# brushed_motor_drivers.net
KiCad netlist of a schematic drawn in Altium Designer
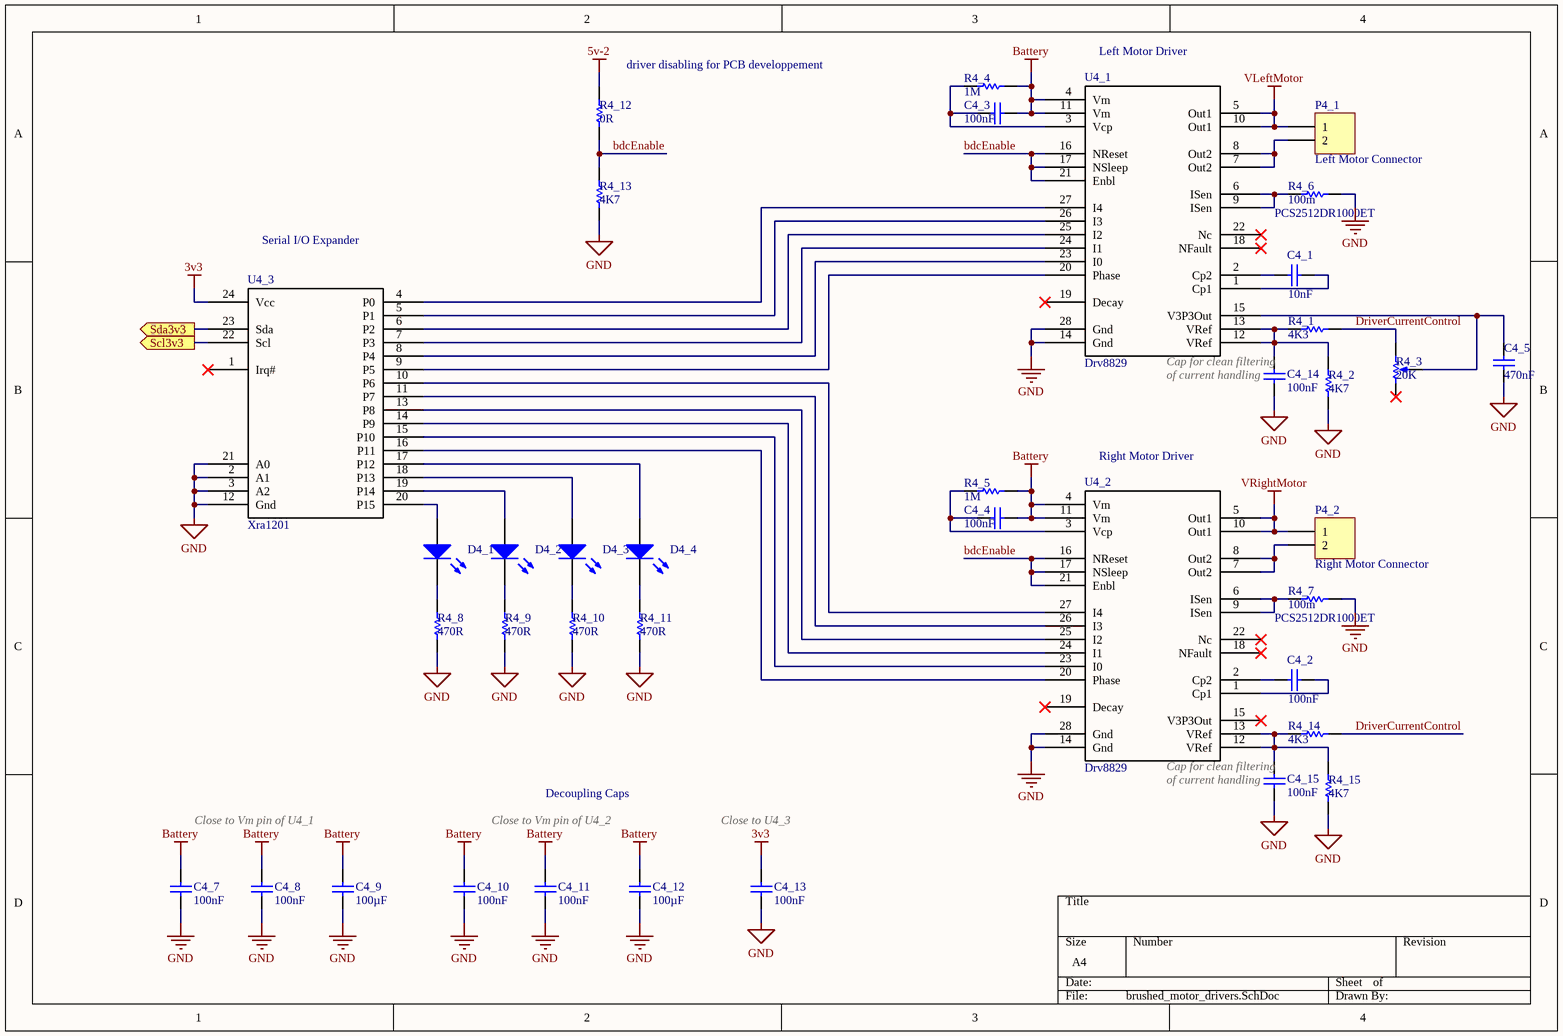
[diagram p0: brushed_motor_drivers.SchDoc]

(export (version "E")
  (design (tool "Eeschema 10.0.6"))
  (components
    (comp (ref "C4_1")
      (value "10nF")
      (footprint "C1206")
      (description "Capacitor")
      (fields (field (name "Comment") "C1206C103M5RACTU") (field (name "PUBLISHER") "Altium Limited"))
      (libsource (lib "Miscellaneous Devices") (part "Cap"))
    )
    (comp (ref "C4_2")
      (value "100nF")
      (footprint "C1206")
      (description "Capacitor")
      (fields (field (name "Comment") "C1206C103M5RACTU") (field (name "PUBLISHER") "Altium Limited"))
      (libsource (lib "Miscellaneous Devices") (part "Cap"))
    )
    (comp (ref "C4_3")
      (value "100nF")
      (footprint "C1206")
      (description "Capacitor")
      (fields (field (name "Comment") "12063C104MAT2A") (field (name "PUBLISHER") "Altium Limited"))
      (libsource (lib "Miscellaneous Devices") (part "Cap"))
    )
    (comp (ref "C4_4")
      (value "100nF")
      (footprint "C1206")
      (description "Capacitor")
      (fields (field (name "Comment") "12063C104MAT2A") (field (name "PUBLISHER") "Altium Limited"))
      (libsource (lib "Miscellaneous Devices") (part "Cap"))
    )
    (comp (ref "C4_5")
      (value "470nF")
      (footprint "C1206")
      (description "Capacitor")
      (fields (field (name "Comment") "C1206C474M5RECAUTO") (field (name "PUBLISHER") "Altium Limited"))
      (libsource (lib "Miscellaneous Devices") (part "Cap"))
    )
    (comp (ref "C4_7")
      (value "100nF")
      (footprint "C1206")
      (description "Capacitor")
      (fields (field (name "Comment") "12063C104MAT2A") (field (name "PUBLISHER") "Altium Limited"))
      (libsource (lib "Miscellaneous Devices") (part "Cap"))
    )
    (comp (ref "C4_8")
      (value "100nF")
      (footprint "C1206")
      (description "Capacitor")
      (fields (field (name "Comment") "12063C104MAT2A") (field (name "PUBLISHER") "Altium Limited"))
      (libsource (lib "Miscellaneous Devices") (part "Cap"))
    )
    (comp (ref "C4_9")
      (value "100µF")
      (footprint "CAP-ELECTRO-530530")
      (description "Capacitor")
      (fields (field (name "Comment") "107AXZ016MQ5") (field (name "PUBLISHER") "Altium Limited"))
      (libsource (lib "Miscellaneous Devices") (part "Cap"))
    )
    (comp (ref "C4_10")
      (value "100nF")
      (footprint "C1206")
      (description "Capacitor")
      (fields (field (name "Comment") "12063C104MAT2A") (field (name "PUBLISHER") "Altium Limited"))
      (libsource (lib "Miscellaneous Devices") (part "Cap"))
    )
    (comp (ref "C4_11")
      (value "100nF")
      (footprint "C1206")
      (description "Capacitor")
      (fields (field (name "Comment") "12063C104MAT2A") (field (name "PUBLISHER") "Altium Limited"))
      (libsource (lib "Miscellaneous Devices") (part "Cap"))
    )
    (comp (ref "C4_12")
      (value "100µF")
      (footprint "CAP-ELECTRO-530530")
      (description "Capacitor")
      (fields (field (name "Comment") "107AXZ016MQ5") (field (name "PUBLISHER") "Altium Limited"))
      (libsource (lib "Miscellaneous Devices") (part "Cap"))
    )
    (comp (ref "C4_13")
      (value "100nF")
      (footprint "C1206")
      (description "Capacitor")
      (fields (field (name "Comment") "12063C104MAT2A") (field (name "PUBLISHER") "Altium Limited"))
      (libsource (lib "Miscellaneous Devices") (part "Cap"))
    )
    (comp (ref "C4_14")
      (value "100nF")
      (footprint "C1206")
      (description "Capacitor")
      (fields (field (name "Comment") "C1206C103M5RACTU") (field (name "PUBLISHER") "Altium Limited"))
      (libsource (lib "Miscellaneous Devices") (part "Cap"))
    )
    (comp (ref "C4_15")
      (value "100nF")
      (footprint "C1206")
      (description "Capacitor")
      (fields (field (name "Comment") "C1206C103M5RACTU") (field (name "PUBLISHER") "Altium Limited"))
      (libsource (lib "Miscellaneous Devices") (part "Cap"))
    )
    (comp (ref "D4_1")
      (value "APT3216QBC/D")
      (footprint "C1206-POLARIZED")
      (description "Typical INFRARED GaAs LED")
      (fields (field (name "PUBLISHER") "Altium Limited"))
      (libsource (lib "Miscellaneous Devices") (part "LED0"))
    )
    (comp (ref "D4_2")
      (value "APT3216QBC/D")
      (footprint "C1206-POLARIZED")
      (description "Typical INFRARED GaAs LED")
      (fields (field (name "PUBLISHER") "Altium Limited"))
      (libsource (lib "Miscellaneous Devices") (part "LED0"))
    )
    (comp (ref "D4_3")
      (value "APT3216QBC/D")
      (footprint "C1206-POLARIZED")
      (description "Typical INFRARED GaAs LED")
      (fields (field (name "PUBLISHER") "Altium Limited"))
      (libsource (lib "Miscellaneous Devices") (part "LED0"))
    )
    (comp (ref "D4_4")
      (value "APT3216QBC/D")
      (footprint "C1206-POLARIZED")
      (description "Typical INFRARED GaAs LED")
      (fields (field (name "PUBLISHER") "Altium Limited"))
      (libsource (lib "Miscellaneous Devices") (part "LED0"))
    )
    (comp (ref "P4_1")
      (value "Left Motor Connector")
      (footprint "HDR1X2-42")
      (description "Header, 2-Pin")
      (fields (field (name "PUBLISHER") "Altium Limited"))
      (libsource (lib "Miscellaneous Connectors") (part "Header 2"))
    )
    (comp (ref "P4_2")
      (value "Right Motor Connector")
      (footprint "HDR1X2-42")
      (description "Header, 2-Pin")
      (fields (field (name "PUBLISHER") "Altium Limited"))
      (libsource (lib "Miscellaneous Connectors") (part "Header 2"))
    )
    (comp (ref "R4_1")
      (value "4K3")
      (footprint "C1206")
      (description "Resistor")
      (fields (field (name "Comment") "Res1") (field (name "PUBLISHER") "Altium Limited"))
      (libsource (lib "Miscellaneous Devices") (part "Res1"))
    )
    (comp (ref "R4_2")
      (value "4K7")
      (footprint "C1206")
      (description "Resistor")
      (fields (field (name "Comment") "Res1") (field (name "PUBLISHER") "Altium Limited"))
      (libsource (lib "Miscellaneous Devices") (part "Res1"))
    )
    (comp (ref "R4_3")
      (value "20K")
      (footprint "ST-32EB")
      (description "Potentiometer")
      (fields (field (name "Comment") "ST32ETB203") (field (name "PUBLISHER") "Altium Limited"))
      (libsource (lib "Miscellaneous Devices") (part "RPot"))
    )
    (comp (ref "R4_4")
      (value "1M")
      (footprint "C1206")
      (description "Resistor")
      (fields (field (name "Comment") "Res1") (field (name "PUBLISHER") "Altium Limited"))
      (libsource (lib "Miscellaneous Devices") (part "Res1"))
    )
    (comp (ref "R4_5")
      (value "1M")
      (footprint "C1206")
      (description "Resistor")
      (fields (field (name "Comment") "Res1") (field (name "PUBLISHER") "Altium Limited"))
      (libsource (lib "Miscellaneous Devices") (part "Res1"))
    )
    (comp (ref "R4_6")
      (value "PCS2512DR1000ET")
      (footprint "2512")
      (description "Resistor")
      (fields (field (name "ALTIUM_VALUE") "100m") (field (name "PUBLISHER") "Altium Limited"))
      (libsource (lib "Miscellaneous Devices") (part "Res1"))
    )
    (comp (ref "R4_7")
      (value "PCS2512DR1000ET")
      (footprint "2512")
      (description "Resistor")
      (fields (field (name "ALTIUM_VALUE") "100m") (field (name "PUBLISHER") "Altium Limited"))
      (libsource (lib "Miscellaneous Devices") (part "Res1"))
    )
    (comp (ref "R4_8")
      (value "470R")
      (footprint "C1206")
      (description "Resistor")
      (fields (field (name "Comment") "Res1") (field (name "PUBLISHER") "Altium Limited"))
      (libsource (lib "Miscellaneous Devices") (part "Res1"))
    )
    (comp (ref "R4_9")
      (value "470R")
      (footprint "C1206")
      (description "Resistor")
      (fields (field (name "Comment") "Res1") (field (name "PUBLISHER") "Altium Limited"))
      (libsource (lib "Miscellaneous Devices") (part "Res1"))
    )
    (comp (ref "R4_10")
      (value "470R")
      (footprint "C1206")
      (description "Resistor")
      (fields (field (name "Comment") "Res1") (field (name "PUBLISHER") "Altium Limited"))
      (libsource (lib "Miscellaneous Devices") (part "Res1"))
    )
    (comp (ref "R4_11")
      (value "470R")
      (footprint "C1206")
      (description "Resistor")
      (fields (field (name "Comment") "Res1") (field (name "PUBLISHER") "Altium Limited"))
      (libsource (lib "Miscellaneous Devices") (part "Res1"))
    )
    (comp (ref "R4_12")
      (value "0R")
      (footprint "C0805")
      (description "Resistor")
      (fields (field (name "Comment") "Res1") (field (name "PUBLISHER") "Altium Limited"))
      (libsource (lib "Miscellaneous Devices") (part "Res1"))
    )
    (comp (ref "R4_13")
      (value "4K7")
      (footprint "C1206")
      (description "Resistor")
      (fields (field (name "Comment") "Res1") (field (name "PUBLISHER") "Altium Limited"))
      (libsource (lib "Miscellaneous Devices") (part "Res1"))
    )
    (comp (ref "R4_14")
      (value "4K3")
      (footprint "C1206")
      (description "Resistor")
      (fields (field (name "Comment") "Res1") (field (name "PUBLISHER") "Altium Limited"))
      (libsource (lib "Miscellaneous Devices") (part "Res1"))
    )
    (comp (ref "R4_15")
      (value "4K7")
      (footprint "C1206")
      (description "Resistor")
      (fields (field (name "Comment") "Res1") (field (name "PUBLISHER") "Altium Limited"))
      (libsource (lib "Miscellaneous Devices") (part "Res1"))
    )
    (comp (ref "U4_1")
      (value "Drv8829")
      (footprint "SOP65P640X120-28N-GROUND_SINK")
      (libsource (lib "projet 6e session") (part "Drv8829"))
    )
    (comp (ref "U4_2")
      (value "Drv8829")
      (footprint "SOP65P640X120-28N-GROUND_SINK")
      (libsource (lib "projet 6e session") (part "Drv8829"))
    )
    (comp (ref "U4_3")
      (value "Xra1201")
      (footprint "SOP65P640X110-24N")
      (libsource (lib "projet 6e session") (part "Xra1201"))
    )
  )
  (nets
    (net (code "1") (name "/DriverCurrentControl") (class "Default")
      (node (ref "R4_1") (pin "2") (pinfunction "2_2") (pintype "passive"))
      (node (ref "R4_14") (pin "2") (pinfunction "2_2") (pintype "passive"))
      (node (ref "R4_3") (pin "2") (pinfunction "BOT_2") (pintype "passive"))
    )
    (net (code "2") (name "/Scl3v3") (class "Default")
      (node (ref "U4_3") (pin "22") (pinfunction "Scl_22") (pintype "passive"))
    )
    (net (code "3") (name "/Sda3v3") (class "Default")
      (node (ref "U4_3") (pin "23") (pinfunction "Sda_23") (pintype "passive"))
    )
    (net (code "4") (name "/bdcEnable") (class "Default")
      (node (ref "R4_12") (pin "2") (pinfunction "2_2") (pintype "passive"))
      (node (ref "R4_13") (pin "1") (pinfunction "1_1") (pintype "passive"))
      (node (ref "U4_1") (pin "16") (pinfunction "NReset_16") (pintype "passive"))
      (node (ref "U4_1") (pin "17") (pinfunction "NSleep_17") (pintype "passive"))
      (node (ref "U4_1") (pin "21") (pinfunction "Enbl_21") (pintype "passive"))
      (node (ref "U4_2") (pin "16") (pinfunction "NReset_16") (pintype "passive"))
      (node (ref "U4_2") (pin "17") (pinfunction "NSleep_17") (pintype "passive"))
      (node (ref "U4_2") (pin "21") (pinfunction "Enbl_21") (pintype "passive"))
    )
    (net (code "5") (name "3v3") (class "Default")
      (node (ref "C4_13") (pin "1") (pinfunction "1_1") (pintype "passive"))
      (node (ref "U4_3") (pin "24") (pinfunction "Vcc_24") (pintype "passive"))
    )
    (net (code "6") (name "5v-2") (class "Default")
      (node (ref "R4_12") (pin "1") (pinfunction "1_1") (pintype "passive"))
    )
    (net (code "7") (name "Battery") (class "Default")
      (node (ref "C4_10") (pin "1") (pinfunction "1_1") (pintype "passive"))
      (node (ref "C4_11") (pin "1") (pinfunction "1_1") (pintype "passive"))
      (node (ref "C4_12") (pin "1") (pinfunction "1_1") (pintype "passive"))
      (node (ref "C4_3") (pin "1") (pinfunction "1_1") (pintype "passive"))
      (node (ref "C4_4") (pin "1") (pinfunction "1_1") (pintype "passive"))
      (node (ref "C4_7") (pin "1") (pinfunction "1_1") (pintype "passive"))
      (node (ref "C4_8") (pin "1") (pinfunction "1_1") (pintype "passive"))
      (node (ref "C4_9") (pin "1") (pinfunction "1_1") (pintype "passive"))
      (node (ref "R4_4") (pin "2") (pinfunction "2_2") (pintype "passive"))
      (node (ref "R4_5") (pin "2") (pinfunction "2_2") (pintype "passive"))
      (node (ref "U4_1") (pin "11") (pinfunction "Vm_11") (pintype "passive"))
      (node (ref "U4_1") (pin "4") (pinfunction "Vm_4") (pintype "passive"))
      (node (ref "U4_2") (pin "11") (pinfunction "Vm_11") (pintype "passive"))
      (node (ref "U4_2") (pin "4") (pinfunction "Vm_4") (pintype "passive"))
    )
    (net (code "8") (name "GND") (class "Default")
      (node (ref "C4_10") (pin "2") (pinfunction "2_2") (pintype "passive"))
      (node (ref "C4_11") (pin "2") (pinfunction "2_2") (pintype "passive"))
      (node (ref "C4_12") (pin "2") (pinfunction "2_2") (pintype "passive"))
      (node (ref "C4_13") (pin "2") (pinfunction "2_2") (pintype "passive"))
      (node (ref "C4_14") (pin "2") (pinfunction "2_2") (pintype "passive"))
      (node (ref "C4_15") (pin "2") (pinfunction "2_2") (pintype "passive"))
      (node (ref "C4_5") (pin "2") (pinfunction "2_2") (pintype "passive"))
      (node (ref "C4_7") (pin "2") (pinfunction "2_2") (pintype "passive"))
      (node (ref "C4_8") (pin "2") (pinfunction "2_2") (pintype "passive"))
      (node (ref "C4_9") (pin "2") (pinfunction "2_2") (pintype "passive"))
      (node (ref "R4_10") (pin "2") (pinfunction "2_2") (pintype "passive"))
      (node (ref "R4_11") (pin "2") (pinfunction "2_2") (pintype "passive"))
      (node (ref "R4_13") (pin "2") (pinfunction "2_2") (pintype "passive"))
      (node (ref "R4_15") (pin "2") (pinfunction "2_2") (pintype "passive"))
      (node (ref "R4_2") (pin "2") (pinfunction "2_2") (pintype "passive"))
      (node (ref "R4_6") (pin "2") (pinfunction "2_2") (pintype "passive"))
      (node (ref "R4_7") (pin "2") (pinfunction "2_2") (pintype "passive"))
      (node (ref "R4_8") (pin "2") (pinfunction "2_2") (pintype "passive"))
      (node (ref "R4_9") (pin "2") (pinfunction "2_2") (pintype "passive"))
      (node (ref "U4_1") (pin "14") (pinfunction "Gnd_14") (pintype "passive"))
      (node (ref "U4_1") (pin "28") (pinfunction "Gnd_28") (pintype "passive"))
      (node (ref "U4_2") (pin "14") (pinfunction "Gnd_14") (pintype "passive"))
      (node (ref "U4_2") (pin "28") (pinfunction "Gnd_28") (pintype "passive"))
      (node (ref "U4_3") (pin "12") (pinfunction "Gnd_12") (pintype "passive"))
      (node (ref "U4_3") (pin "2") (pinfunction "A1_2") (pintype "passive"))
      (node (ref "U4_3") (pin "21") (pinfunction "A0_21") (pintype "passive"))
      (node (ref "U4_3") (pin "3") (pinfunction "A2_3") (pintype "passive"))
    )
    (net (code "9") (name "Net-(C4_14-Pad1)") (class "Default")
      (node (ref "C4_14") (pin "1") (pinfunction "1_1") (pintype "passive"))
      (node (ref "R4_1") (pin "1") (pinfunction "1_1") (pintype "passive"))
      (node (ref "R4_2") (pin "1") (pinfunction "1_1") (pintype "passive"))
      (node (ref "U4_1") (pin "12") (pinfunction "VRef_12") (pintype "passive"))
      (node (ref "U4_1") (pin "13") (pinfunction "VRef_13") (pintype "passive"))
    )
    (net (code "10") (name "Net-(C4_15-Pad1)") (class "Default")
      (node (ref "C4_15") (pin "1") (pinfunction "1_1") (pintype "passive"))
      (node (ref "R4_14") (pin "1") (pinfunction "1_1") (pintype "passive"))
      (node (ref "R4_15") (pin "1") (pinfunction "1_1") (pintype "passive"))
      (node (ref "U4_2") (pin "12") (pinfunction "VRef_12") (pintype "passive"))
      (node (ref "U4_2") (pin "13") (pinfunction "VRef_13") (pintype "passive"))
    )
    (net (code "11") (name "Net-(D4_1-A)") (class "Default")
      (node (ref "D4_1") (pin "1") (pinfunction "A_1") (pintype "passive"))
      (node (ref "U4_3") (pin "20") (pinfunction "P15_20") (pintype "passive"))
    )
    (net (code "12") (name "Net-(D4_1-K)") (class "Default")
      (node (ref "D4_1") (pin "2") (pinfunction "K_2") (pintype "passive"))
      (node (ref "R4_8") (pin "1") (pinfunction "1_1") (pintype "passive"))
    )
    (net (code "13") (name "Net-(D4_2-A)") (class "Default")
      (node (ref "D4_2") (pin "1") (pinfunction "A_1") (pintype "passive"))
      (node (ref "U4_3") (pin "19") (pinfunction "P14_19") (pintype "passive"))
    )
    (net (code "14") (name "Net-(D4_2-K)") (class "Default")
      (node (ref "D4_2") (pin "2") (pinfunction "K_2") (pintype "passive"))
      (node (ref "R4_9") (pin "1") (pinfunction "1_1") (pintype "passive"))
    )
    (net (code "15") (name "Net-(D4_3-A)") (class "Default")
      (node (ref "D4_3") (pin "1") (pinfunction "A_1") (pintype "passive"))
      (node (ref "U4_3") (pin "18") (pinfunction "P13_18") (pintype "passive"))
    )
    (net (code "16") (name "Net-(D4_3-K)") (class "Default")
      (node (ref "D4_3") (pin "2") (pinfunction "K_2") (pintype "passive"))
      (node (ref "R4_10") (pin "1") (pinfunction "1_1") (pintype "passive"))
    )
    (net (code "17") (name "Net-(D4_4-A)") (class "Default")
      (node (ref "D4_4") (pin "1") (pinfunction "A_1") (pintype "passive"))
      (node (ref "U4_3") (pin "17") (pinfunction "P12_17") (pintype "passive"))
    )
    (net (code "18") (name "Net-(D4_4-K)") (class "Default")
      (node (ref "D4_4") (pin "2") (pinfunction "K_2") (pintype "passive"))
      (node (ref "R4_11") (pin "1") (pinfunction "1_1") (pintype "passive"))
    )
    (net (code "19") (name "Net-(P4_1-Pad2)") (class "Default")
      (node (ref "P4_1") (pin "2") (pinfunction "2_2") (pintype "passive"))
      (node (ref "U4_1") (pin "7") (pinfunction "Out2_7") (pintype "passive"))
      (node (ref "U4_1") (pin "8") (pinfunction "Out2_8") (pintype "passive"))
    )
    (net (code "20") (name "Net-(P4_2-Pad2)") (class "Default")
      (node (ref "P4_2") (pin "2") (pinfunction "2_2") (pintype "passive"))
      (node (ref "U4_2") (pin "7") (pinfunction "Out2_7") (pintype "passive"))
      (node (ref "U4_2") (pin "8") (pinfunction "Out2_8") (pintype "passive"))
    )
    (net (code "21") (name "Net-(R4_3-TAP)") (class "Default")
      (node (ref "C4_5") (pin "1") (pinfunction "1_1") (pintype "passive"))
      (node (ref "R4_3") (pin "3") (pinfunction "TAP_3") (pintype "passive"))
      (node (ref "U4_1") (pin "15") (pinfunction "V3P3Out_15") (pintype "passive"))
    )
    (net (code "22") (name "Net-(R4_6-Pad1)") (class "Default")
      (node (ref "R4_6") (pin "1") (pinfunction "1_1") (pintype "passive"))
      (node (ref "U4_1") (pin "6") (pinfunction "ISen_6") (pintype "passive"))
      (node (ref "U4_1") (pin "9") (pinfunction "ISen_9") (pintype "passive"))
    )
    (net (code "23") (name "Net-(R4_7-Pad1)") (class "Default")
      (node (ref "R4_7") (pin "1") (pinfunction "1_1") (pintype "passive"))
      (node (ref "U4_2") (pin "6") (pinfunction "ISen_6") (pintype "passive"))
      (node (ref "U4_2") (pin "9") (pinfunction "ISen_9") (pintype "passive"))
    )
    (net (code "24") (name "Net-(U4_1-Cp1)") (class "Default")
      (node (ref "C4_1") (pin "1") (pinfunction "1_1") (pintype "passive"))
      (node (ref "U4_1") (pin "1") (pinfunction "Cp1_1") (pintype "passive"))
    )
    (net (code "25") (name "Net-(U4_1-Cp2)") (class "Default")
      (node (ref "C4_1") (pin "2") (pinfunction "2_2") (pintype "passive"))
      (node (ref "U4_1") (pin "2") (pinfunction "Cp2_2") (pintype "passive"))
    )
    (net (code "26") (name "Net-(U4_1-I0)") (class "Default")
      (node (ref "U4_1") (pin "23") (pinfunction "I0_23") (pintype "passive"))
      (node (ref "U4_3") (pin "8") (pinfunction "P4_8") (pintype "passive"))
    )
    (net (code "27") (name "Net-(U4_1-I1)") (class "Default")
      (node (ref "U4_1") (pin "24") (pinfunction "I1_24") (pintype "passive"))
      (node (ref "U4_3") (pin "7") (pinfunction "P3_7") (pintype "passive"))
    )
    (net (code "28") (name "Net-(U4_1-I2)") (class "Default")
      (node (ref "U4_1") (pin "25") (pinfunction "I2_25") (pintype "passive"))
      (node (ref "U4_3") (pin "6") (pinfunction "P2_6") (pintype "passive"))
    )
    (net (code "29") (name "Net-(U4_1-I3)") (class "Default")
      (node (ref "U4_1") (pin "26") (pinfunction "I3_26") (pintype "passive"))
      (node (ref "U4_3") (pin "5") (pinfunction "P1_5") (pintype "passive"))
    )
    (net (code "30") (name "Net-(U4_1-I4)") (class "Default")
      (node (ref "U4_1") (pin "27") (pinfunction "I4_27") (pintype "passive"))
      (node (ref "U4_3") (pin "4") (pinfunction "P0_4") (pintype "passive"))
    )
    (net (code "31") (name "Net-(U4_1-Phase)") (class "Default")
      (node (ref "U4_1") (pin "20") (pinfunction "Phase_20") (pintype "passive"))
      (node (ref "U4_3") (pin "9") (pinfunction "P5_9") (pintype "passive"))
    )
    (net (code "32") (name "Net-(U4_1-Vcp)") (class "Default")
      (node (ref "C4_3") (pin "2") (pinfunction "2_2") (pintype "passive"))
      (node (ref "R4_4") (pin "1") (pinfunction "1_1") (pintype "passive"))
      (node (ref "U4_1") (pin "3") (pinfunction "Vcp_3") (pintype "passive"))
    )
    (net (code "33") (name "Net-(U4_2-Cp1)") (class "Default")
      (node (ref "C4_2") (pin "1") (pinfunction "1_1") (pintype "passive"))
      (node (ref "U4_2") (pin "1") (pinfunction "Cp1_1") (pintype "passive"))
    )
    (net (code "34") (name "Net-(U4_2-Cp2)") (class "Default")
      (node (ref "C4_2") (pin "2") (pinfunction "2_2") (pintype "passive"))
      (node (ref "U4_2") (pin "2") (pinfunction "Cp2_2") (pintype "passive"))
    )
    (net (code "35") (name "Net-(U4_2-I0)") (class "Default")
      (node (ref "U4_2") (pin "23") (pinfunction "I0_23") (pintype "passive"))
      (node (ref "U4_3") (pin "15") (pinfunction "P10_15") (pintype "passive"))
    )
    (net (code "36") (name "Net-(U4_2-I1)") (class "Default")
      (node (ref "U4_2") (pin "24") (pinfunction "I1_24") (pintype "passive"))
      (node (ref "U4_3") (pin "14") (pinfunction "P9_14") (pintype "passive"))
    )
    (net (code "37") (name "Net-(U4_2-I2)") (class "Default")
      (node (ref "U4_2") (pin "25") (pinfunction "I2_25") (pintype "passive"))
      (node (ref "U4_3") (pin "13") (pinfunction "P8_13") (pintype "passive"))
    )
    (net (code "38") (name "Net-(U4_2-I3)") (class "Default")
      (node (ref "U4_2") (pin "26") (pinfunction "I3_26") (pintype "passive"))
      (node (ref "U4_3") (pin "11") (pinfunction "P7_11") (pintype "passive"))
    )
    (net (code "39") (name "Net-(U4_2-I4)") (class "Default")
      (node (ref "U4_2") (pin "27") (pinfunction "I4_27") (pintype "passive"))
      (node (ref "U4_3") (pin "10") (pinfunction "P6_10") (pintype "passive"))
    )
    (net (code "40") (name "Net-(U4_2-Phase)") (class "Default")
      (node (ref "U4_2") (pin "20") (pinfunction "Phase_20") (pintype "passive"))
      (node (ref "U4_3") (pin "16") (pinfunction "P11_16") (pintype "passive"))
    )
    (net (code "41") (name "Net-(U4_2-Vcp)") (class "Default")
      (node (ref "C4_4") (pin "2") (pinfunction "2_2") (pintype "passive"))
      (node (ref "R4_5") (pin "1") (pinfunction "1_1") (pintype "passive"))
      (node (ref "U4_2") (pin "3") (pinfunction "Vcp_3") (pintype "passive"))
    )
    (net (code "42") (name "VLeftMotor") (class "Default")
      (node (ref "P4_1") (pin "1") (pinfunction "1_1") (pintype "passive"))
      (node (ref "U4_1") (pin "10") (pinfunction "Out1_10") (pintype "passive"))
      (node (ref "U4_1") (pin "5") (pinfunction "Out1_5") (pintype "passive"))
    )
    (net (code "43") (name "VRightMotor") (class "Default")
      (node (ref "P4_2") (pin "1") (pinfunction "1_1") (pintype "passive"))
      (node (ref "U4_2") (pin "10") (pinfunction "Out1_10") (pintype "passive"))
      (node (ref "U4_2") (pin "5") (pinfunction "Out1_5") (pintype "passive"))
    )
    (net (code "44") (name "unconnected-(R4_3-TOP-Pad1)") (class "Default")
      (node (ref "R4_3") (pin "1") (pinfunction "TOP_1") (pintype "passive+no_connect"))
    )
    (net (code "45") (name "unconnected-(U4_1-Decay-Pad19)") (class "Default")
      (node (ref "U4_1") (pin "19") (pinfunction "Decay_19") (pintype "passive+no_connect"))
    )
    (net (code "46") (name "unconnected-(U4_1-NFault-Pad18)") (class "Default")
      (node (ref "U4_1") (pin "18") (pinfunction "NFault_18") (pintype "passive+no_connect"))
    )
    (net (code "47") (name "unconnected-(U4_1-Nc-Pad22)") (class "Default")
      (node (ref "U4_1") (pin "22") (pinfunction "Nc_22") (pintype "passive+no_connect"))
    )
    (net (code "48") (name "unconnected-(U4_2-Decay-Pad19)") (class "Default")
      (node (ref "U4_2") (pin "19") (pinfunction "Decay_19") (pintype "passive+no_connect"))
    )
    (net (code "49") (name "unconnected-(U4_2-NFault-Pad18)") (class "Default")
      (node (ref "U4_2") (pin "18") (pinfunction "NFault_18") (pintype "passive+no_connect"))
    )
    (net (code "50") (name "unconnected-(U4_2-Nc-Pad22)") (class "Default")
      (node (ref "U4_2") (pin "22") (pinfunction "Nc_22") (pintype "passive+no_connect"))
    )
    (net (code "51") (name "unconnected-(U4_2-V3P3Out-Pad15)") (class "Default")
      (node (ref "U4_2") (pin "15") (pinfunction "V3P3Out_15") (pintype "passive+no_connect"))
    )
    (net (code "52") (name "unconnected-(U4_3-Irq#-Pad1)") (class "Default")
      (node (ref "U4_3") (pin "1") (pinfunction "Irq#_1") (pintype "passive+no_connect"))
    )
  )
)
